# encoder_as5047p.net
KiCad netlist of a schematic drawn in EAGLE
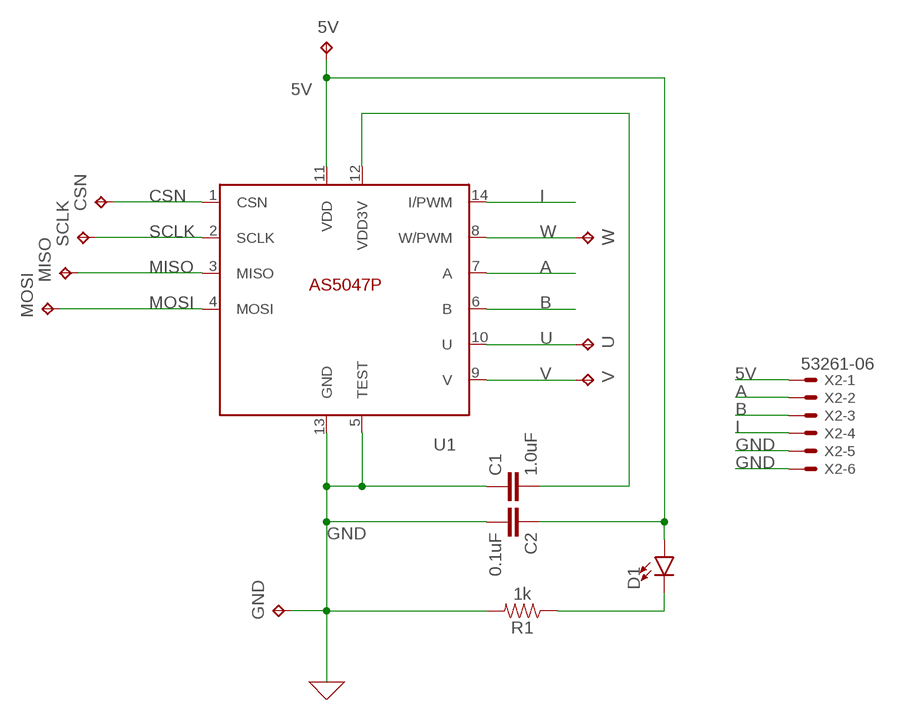
[diagram p0: schematic, sheet 1]

(export (version "E")
  (design (tool "Eeschema 10.0.6"))
  (components
    (comp (ref "5V")
      (value "TPTP12R")
      (footprint "eagle-import:TP12R")
      (libsource (lib "eagle-import") (part "TPTP12R"))
    )
    (comp (ref "C1")
      (value "1.0uF")
      (footprint "eagle-import:0603")
      (libsource (lib "eagle-import") (part "1.0UF-0603-16V-10%"))
    )
    (comp (ref "C2")
      (value "0.1uF")
      (footprint "eagle-import:0603")
      (libsource (lib "eagle-import") (part "0.1UF-0603-25V-(+80/-20%)"))
    )
    (comp (ref "CSN")
      (value "TPTP12R")
      (footprint "eagle-import:TP12R")
      (libsource (lib "eagle-import") (part "TPTP12R"))
    )
    (comp (ref "D1")
      (value "LED0603")
      (footprint "eagle-import:LED-0603")
      (libsource (lib "eagle-import") (part "LED0603"))
    )
    (comp (ref "GND")
      (value "TPTP12R")
      (footprint "eagle-import:TP12R")
      (libsource (lib "eagle-import") (part "TPTP12R"))
    )
    (comp (ref "MISO")
      (value "TPTP12R")
      (footprint "eagle-import:TP12R")
      (libsource (lib "eagle-import") (part "TPTP12R"))
    )
    (comp (ref "MOSI")
      (value "TPTP12R")
      (footprint "eagle-import:TP12R")
      (libsource (lib "eagle-import") (part "TPTP12R"))
    )
    (comp (ref "R1")
      (value "1k")
      (footprint "eagle-import:0603")
      (libsource (lib "eagle-import") (part "1KOHM-0603-1/10W-1%"))
    )
    (comp (ref "SCLK")
      (value "TPTP12R")
      (footprint "eagle-import:TP12R")
      (libsource (lib "eagle-import") (part "TPTP12R"))
    )
    (comp (ref "U")
      (value "TPTP12R")
      (footprint "eagle-import:TP12R")
      (libsource (lib "eagle-import") (part "TPTP12R"))
    )
    (comp (ref "U1")
      (value "AS5047P")
      (footprint "eagle-import:TSSOP14")
      (libsource (lib "eagle-import") (part "AS5047P"))
    )
    (comp (ref "V")
      (value "TPTP12R")
      (footprint "eagle-import:TP12R")
      (libsource (lib "eagle-import") (part "TPTP12R"))
    )
    (comp (ref "W")
      (value "TPTP12R")
      (footprint "eagle-import:TP12R")
      (libsource (lib "eagle-import") (part "TPTP12R"))
    )
    (comp (ref "X2")
      (value "53261-06")
      (footprint "eagle-import:53261-06")
      (fields (field (name "MF") "MOLEX"))
      (libsource (lib "eagle-import") (part "53?-06261"))
    )
  )
  (nets
    (net (code "1") (name "/5V") (class "Default")
      (node (ref "5V") (pin "TP") (pinfunction "TP_TP") (pintype "input"))
      (node (ref "C2") (pin "1") (pinfunction "1_1") (pintype "passive"))
      (node (ref "D1") (pin "A") (pinfunction "A_A") (pintype "passive"))
      (node (ref "U1") (pin "11") (pinfunction "VDD_11") (pintype "power_in"))
      (node (ref "X2") (pin "1") (pinfunction "S_1") (pintype "passive"))
    )
    (net (code "2") (name "/A") (class "Default")
      (node (ref "U1") (pin "7") (pinfunction "A_7") (pintype "output"))
      (node (ref "X2") (pin "2") (pinfunction "S_2") (pintype "passive"))
    )
    (net (code "3") (name "/B") (class "Default")
      (node (ref "U1") (pin "6") (pinfunction "B_6") (pintype "output"))
      (node (ref "X2") (pin "3") (pinfunction "S_3") (pintype "passive"))
    )
    (net (code "4") (name "/CSN") (class "Default")
      (node (ref "CSN") (pin "TP") (pinfunction "TP_TP") (pintype "input"))
      (node (ref "U1") (pin "1") (pinfunction "CSN_1") (pintype "input"))
    )
    (net (code "5") (name "/I") (class "Default")
      (node (ref "U1") (pin "14") (pinfunction "I/PWM_14") (pintype "output"))
      (node (ref "X2") (pin "4") (pinfunction "S_4") (pintype "passive"))
    )
    (net (code "6") (name "/MISO") (class "Default")
      (node (ref "MISO") (pin "TP") (pinfunction "TP_TP") (pintype "input"))
      (node (ref "U1") (pin "3") (pinfunction "MISO_3") (pintype "output"))
    )
    (net (code "7") (name "/MOSI") (class "Default")
      (node (ref "MOSI") (pin "TP") (pinfunction "TP_TP") (pintype "input"))
      (node (ref "U1") (pin "4") (pinfunction "MOSI_4") (pintype "input"))
    )
    (net (code "8") (name "/SCLK") (class "Default")
      (node (ref "SCLK") (pin "TP") (pinfunction "TP_TP") (pintype "input"))
      (node (ref "U1") (pin "2") (pinfunction "SCLK_2") (pintype "input"))
    )
    (net (code "9") (name "/U") (class "Default")
      (node (ref "U") (pin "TP") (pinfunction "TP_TP") (pintype "input"))
      (node (ref "U1") (pin "10") (pinfunction "U_10") (pintype "output"))
    )
    (net (code "10") (name "/V") (class "Default")
      (node (ref "U1") (pin "9") (pinfunction "V_9") (pintype "output"))
      (node (ref "V") (pin "TP") (pinfunction "TP_TP") (pintype "input"))
    )
    (net (code "11") (name "/W") (class "Default")
      (node (ref "U1") (pin "8") (pinfunction "W/PWM_8") (pintype "output"))
      (node (ref "W") (pin "TP") (pinfunction "TP_TP") (pintype "input"))
    )
    (net (code "12") (name "GND") (class "Default")
      (node (ref "C1") (pin "1") (pinfunction "1_1") (pintype "passive"))
      (node (ref "C2") (pin "2") (pinfunction "2_2") (pintype "passive"))
      (node (ref "GND") (pin "TP") (pinfunction "TP_TP") (pintype "input"))
      (node (ref "R1") (pin "2") (pinfunction "2_2") (pintype "passive"))
      (node (ref "U1") (pin "13") (pinfunction "GND_13") (pintype "power_in"))
      (node (ref "U1") (pin "5") (pinfunction "TEST_5") (pintype "power_in"))
      (node (ref "X2") (pin "5") (pinfunction "S_5") (pintype "passive"))
      (node (ref "X2") (pin "6") (pinfunction "S_6") (pintype "passive"))
    )
    (net (code "13") (name "Net-(D1-PadC)") (class "Default")
      (node (ref "D1") (pin "C") (pinfunction "C_C") (pintype "passive"))
      (node (ref "R1") (pin "1") (pinfunction "1_1") (pintype "passive"))
    )
    (net (code "14") (name "Net-(U1-VDD3V)") (class "Default")
      (node (ref "C1") (pin "2") (pinfunction "2_2") (pintype "passive"))
      (node (ref "U1") (pin "12") (pinfunction "VDD3V_12") (pintype "power_in"))
    )
  )
)
